# 02_CV25_SOM.net
KiCad netlist of a schematic drawn in Altium Designer
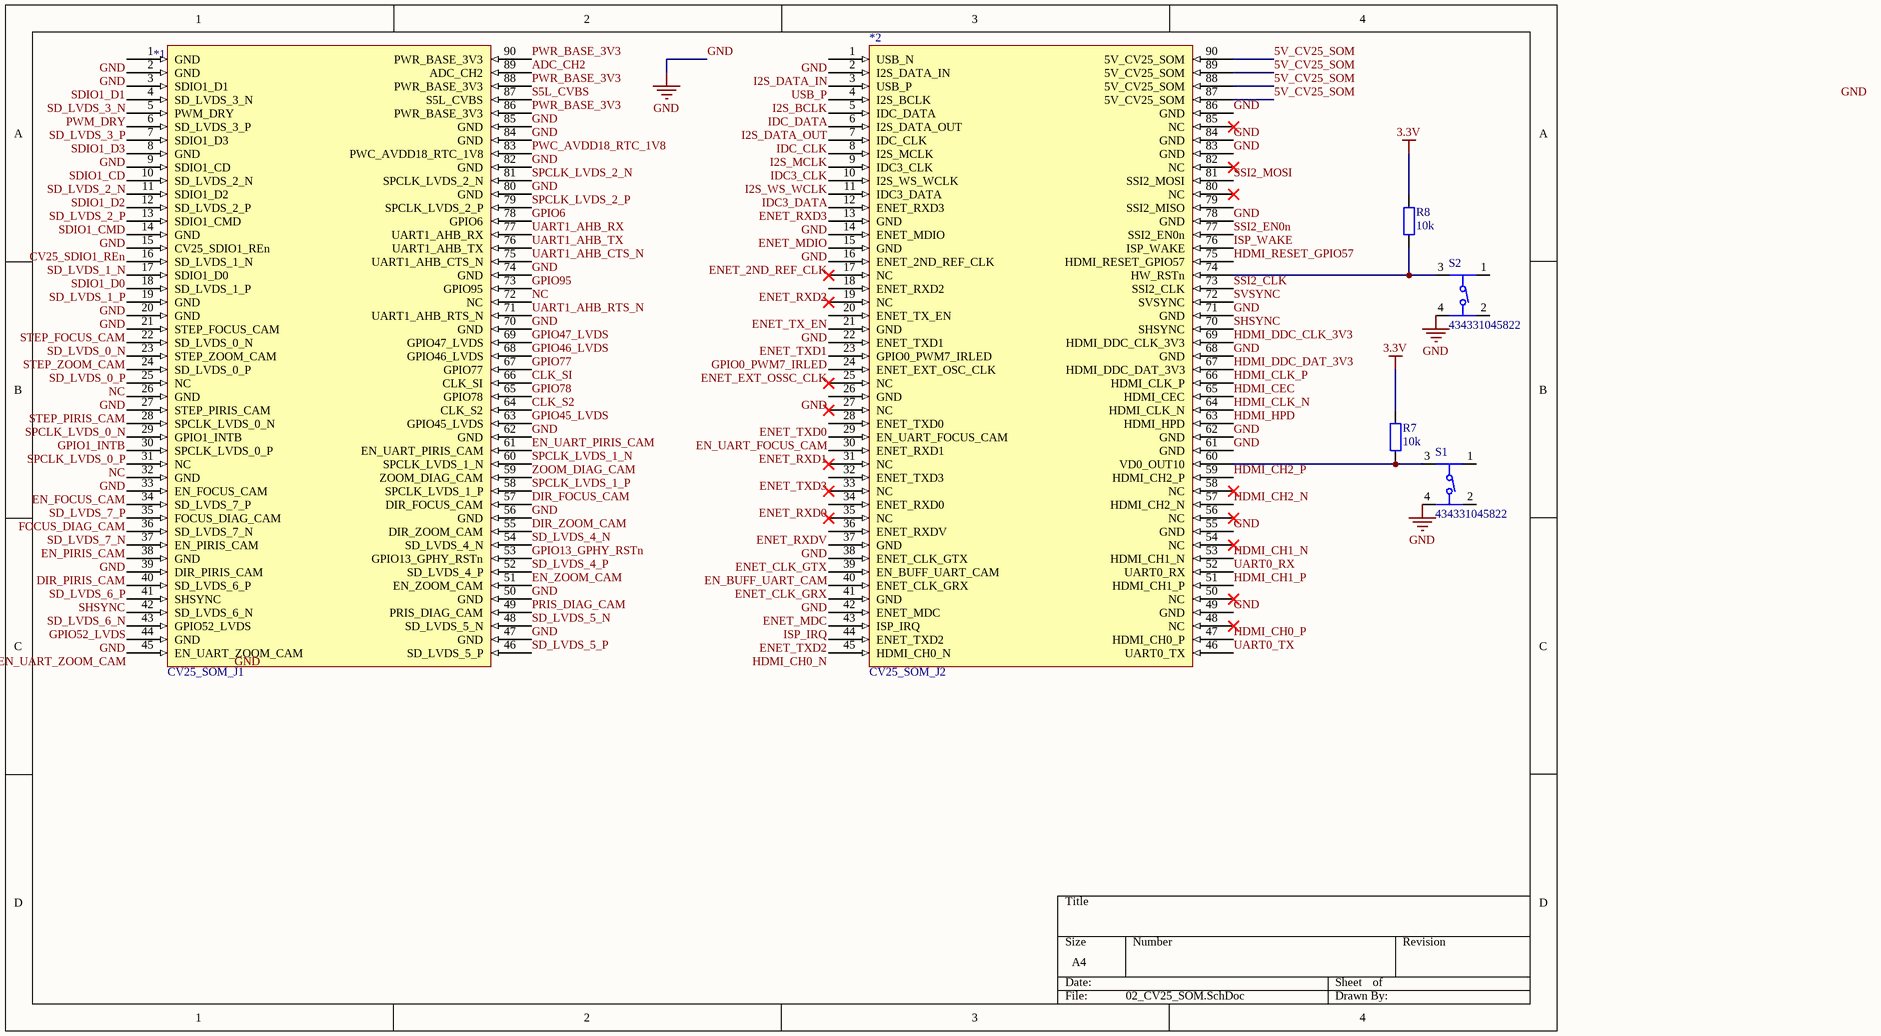
[diagram p0: 02_CV25_SOM.SchDoc]

(export (version "E")
  (design (tool "Eeschema 10.0.6"))
  (components
    (comp (ref "*1")
      (value "CV25_SOM_J1")
      (footprint "HIROSE_DF40C-90DS-0.4V(51)")
      (libsource (lib "MyLib") (part "CV25_SOM_J1"))
    )
    (comp (ref "*2")
      (value "CV25_SOM_J2")
      (footprint "HIROSE_DF40C-90DS-0.4V(51)")
      (libsource (lib "MyLib") (part "CV25_SOM_J2"))
    )
    (comp (ref "R7")
      (value "10k")
      (footprint "tro smd 0603")
      (description "Dán")
      (libsource (lib "Altium_Lib_by_KhueNguyenCreator") (part "Tro 0603 1% 10k"))
    )
    (comp (ref "R8")
      (value "10k")
      (footprint "tro smd 0603")
      (description "Dán")
      (libsource (lib "Altium_Lib_by_KhueNguyenCreator") (part "Tro 0603 1% 10k"))
    )
    (comp (ref "S1")
      (value "434331045822")
      (footprint "4343X10458XX")
      (fields (field (name "MF") "{'manufacturer': u'~{W}xfcrth Elektronik'}"))
      (libsource (lib "434331045822") (part "434331045822"))
    )
    (comp (ref "S2")
      (value "434331045822")
      (footprint "4343X10458XX")
      (fields (field (name "MF") "{'manufacturer': u'~{W}xfcrth Elektronik'}"))
      (libsource (lib "434331045822") (part "434331045822"))
    )
  )
  (nets
    (net (code "1") (name "/5V_CV25_SOM") (class "Default")
      (node (ref "*2") (pin "87") (pinfunction "5V_CV25_SOM_87") (pintype "input"))
      (node (ref "*2") (pin "88") (pinfunction "5V_CV25_SOM_88") (pintype "input"))
      (node (ref "*2") (pin "89") (pinfunction "5V_CV25_SOM_89") (pintype "input"))
      (node (ref "*2") (pin "90") (pinfunction "5V_CV25_SOM_90") (pintype "input"))
    )
    (net (code "2") (name "/ADC_CH2") (class "Default")
      (node (ref "*1") (pin "89") (pinfunction "ADC_CH2_89") (pintype "input"))
    )
    (net (code "3") (name "/CLK_S2") (class "Default")
      (node (ref "*1") (pin "64") (pinfunction "CLK_S2_64") (pintype "input"))
    )
    (net (code "4") (name "/CLK_SI") (class "Default")
      (node (ref "*1") (pin "66") (pinfunction "CLK_SI_66") (pintype "input"))
    )
    (net (code "5") (name "/CV25_SDIO1_REn") (class "Default")
      (node (ref "*1") (pin "15") (pinfunction "CV25_SDIO1_REn_15") (pintype "input"))
    )
    (net (code "6") (name "/DIR_FOCUS_CAM") (class "Default")
      (node (ref "*1") (pin "57") (pinfunction "DIR_FOCUS_CAM_57") (pintype "input"))
    )
    (net (code "7") (name "/DIR_PIRIS_CAM") (class "Default")
      (node (ref "*1") (pin "39") (pinfunction "DIR_PIRIS_CAM_39") (pintype "input"))
    )
    (net (code "8") (name "/DIR_ZOOM_CAM") (class "Default")
      (node (ref "*1") (pin "55") (pinfunction "DIR_ZOOM_CAM_55") (pintype "input"))
    )
    (net (code "9") (name "/ENET_2ND_REF_CLK") (class "Default")
      (node (ref "*2") (pin "16") (pinfunction "ENET_2ND_REF_CLK_16") (pintype "input"))
    )
    (net (code "10") (name "/ENET_CLK_GRX") (class "Default")
      (node (ref "*2") (pin "40") (pinfunction "ENET_CLK_GRX_40") (pintype "input"))
    )
    (net (code "11") (name "/ENET_CLK_GTX") (class "Default")
      (node (ref "*2") (pin "38") (pinfunction "ENET_CLK_GTX_38") (pintype "input"))
    )
    (net (code "12") (name "/ENET_EXT_OSSC_CLK") (class "Default")
      (node (ref "*2") (pin "24") (pinfunction "ENET_EXT_OSC_CLK_24") (pintype "input"))
    )
    (net (code "13") (name "/ENET_MDC") (class "Default")
      (node (ref "*2") (pin "42") (pinfunction "ENET_MDC_42") (pintype "input"))
    )
    (net (code "14") (name "/ENET_MDIO") (class "Default")
      (node (ref "*2") (pin "14") (pinfunction "ENET_MDIO_14") (pintype "input"))
    )
    (net (code "15") (name "/ENET_RXD0") (class "Default")
      (node (ref "*2") (pin "34") (pinfunction "ENET_RXD0_34") (pintype "input"))
    )
    (net (code "16") (name "/ENET_RXD1") (class "Default")
      (node (ref "*2") (pin "30") (pinfunction "ENET_RXD1_30") (pintype "input"))
    )
    (net (code "17") (name "/ENET_RXD2") (class "Default")
      (node (ref "*2") (pin "18") (pinfunction "ENET_RXD2_18") (pintype "input"))
    )
    (net (code "18") (name "/ENET_RXD3") (class "Default")
      (node (ref "*2") (pin "12") (pinfunction "ENET_RXD3_12") (pintype "input"))
    )
    (net (code "19") (name "/ENET_RXDV") (class "Default")
      (node (ref "*2") (pin "36") (pinfunction "ENET_RXDV_36") (pintype "input"))
    )
    (net (code "20") (name "/ENET_TXD0") (class "Default")
      (node (ref "*2") (pin "28") (pinfunction "ENET_TXD0_28") (pintype "input"))
    )
    (net (code "21") (name "/ENET_TXD1") (class "Default")
      (node (ref "*2") (pin "22") (pinfunction "ENET_TXD1_22") (pintype "input"))
    )
    (net (code "22") (name "/ENET_TXD2") (class "Default")
      (node (ref "*2") (pin "44") (pinfunction "ENET_TXD2_44") (pintype "input"))
    )
    (net (code "23") (name "/ENET_TXD3") (class "Default")
      (node (ref "*2") (pin "32") (pinfunction "ENET_TXD3_32") (pintype "input"))
    )
    (net (code "24") (name "/ENET_TX_EN") (class "Default")
      (node (ref "*2") (pin "20") (pinfunction "ENET_TX_EN_20") (pintype "input"))
    )
    (net (code "25") (name "/EN_BUFF_UART_CAM") (class "Default")
      (node (ref "*2") (pin "39") (pinfunction "EN_BUFF_UART_CAM_39") (pintype "input"))
    )
    (net (code "26") (name "/EN_FOCUS_CAM") (class "Default")
      (node (ref "*1") (pin "33") (pinfunction "EN_FOCUS_CAM_33") (pintype "input"))
    )
    (net (code "27") (name "/EN_PIRIS_CAM") (class "Default")
      (node (ref "*1") (pin "37") (pinfunction "EN_PIRIS_CAM_37") (pintype "input"))
    )
    (net (code "28") (name "/EN_UART_FOCUS_CAM") (class "Default")
      (node (ref "*2") (pin "29") (pinfunction "EN_UART_FOCUS_CAM_29") (pintype "input"))
    )
    (net (code "29") (name "/EN_UART_PIRIS_CAM") (class "Default")
      (node (ref "*1") (pin "61") (pinfunction "EN_UART_PIRIS_CAM_61") (pintype "input"))
    )
    (net (code "30") (name "/EN_UART_ZOOM_CAM") (class "Default")
      (node (ref "*1") (pin "45") (pinfunction "EN_UART_ZOOM_CAM_45") (pintype "input"))
    )
    (net (code "31") (name "/EN_ZOOM_CAM") (class "Default")
      (node (ref "*1") (pin "51") (pinfunction "EN_ZOOM_CAM_51") (pintype "input"))
    )
    (net (code "32") (name "/FOCUS_DIAG_CAM") (class "Default")
      (node (ref "*1") (pin "35") (pinfunction "FOCUS_DIAG_CAM_35") (pintype "input"))
    )
    (net (code "33") (name "/GPIO0_PWM7_IRLED") (class "Default")
      (node (ref "*2") (pin "23") (pinfunction "GPIO0_PWM7_IRLED_23") (pintype "input"))
    )
    (net (code "34") (name "/GPIO1_INTB") (class "Default")
      (node (ref "*1") (pin "29") (pinfunction "GPIO1_INTB_29") (pintype "input"))
    )
    (net (code "35") (name "/GPIO6") (class "Default")
      (node (ref "*1") (pin "78") (pinfunction "GPIO6_78") (pintype "input"))
    )
    (net (code "36") (name "/GPIO13_GPHY_RSTn") (class "Default")
      (node (ref "*1") (pin "53") (pinfunction "GPIO13_GPHY_RSTn_53") (pintype "input"))
    )
    (net (code "37") (name "/GPIO45_LVDS") (class "Default")
      (node (ref "*1") (pin "63") (pinfunction "GPIO45_LVDS_63") (pintype "input"))
    )
    (net (code "38") (name "/GPIO46_LVDS") (class "Default")
      (node (ref "*1") (pin "68") (pinfunction "GPIO46_LVDS_68") (pintype "input"))
    )
    (net (code "39") (name "/GPIO47_LVDS") (class "Default")
      (node (ref "*1") (pin "69") (pinfunction "GPIO47_LVDS_69") (pintype "input"))
    )
    (net (code "40") (name "/GPIO52_LVDS") (class "Default")
      (node (ref "*1") (pin "43") (pinfunction "GPIO52_LVDS_43") (pintype "input"))
    )
    (net (code "41") (name "/GPIO77") (class "Default")
      (node (ref "*1") (pin "67") (pinfunction "GPIO77_67") (pintype "input"))
    )
    (net (code "42") (name "/GPIO78") (class "Default")
      (node (ref "*1") (pin "65") (pinfunction "GPIO78_65") (pintype "input"))
    )
    (net (code "43") (name "/GPIO95") (class "Default")
      (node (ref "*1") (pin "73") (pinfunction "GPIO95_73") (pintype "input"))
    )
    (net (code "44") (name "/HDMI_CEC") (class "Default")
      (node (ref "*2") (pin "65") (pinfunction "HDMI_CEC_65") (pintype "input"))
    )
    (net (code "45") (name "/HDMI_CH0_N") (class "Default")
      (node (ref "*2") (pin "45") (pinfunction "HDMI_CH0_N_45") (pintype "input"))
    )
    (net (code "46") (name "/HDMI_CH0_P") (class "Default")
      (node (ref "*2") (pin "47") (pinfunction "HDMI_CH0_P_47") (pintype "input"))
    )
    (net (code "47") (name "/HDMI_CH1_N") (class "Default")
      (node (ref "*2") (pin "53") (pinfunction "HDMI_CH1_N_53") (pintype "input"))
    )
    (net (code "48") (name "/HDMI_CH1_P") (class "Default")
      (node (ref "*2") (pin "51") (pinfunction "HDMI_CH1_P_51") (pintype "input"))
    )
    (net (code "49") (name "/HDMI_CH2_N") (class "Default")
      (node (ref "*2") (pin "57") (pinfunction "HDMI_CH2_N_57") (pintype "input"))
    )
    (net (code "50") (name "/HDMI_CH2_P") (class "Default")
      (node (ref "*2") (pin "59") (pinfunction "HDMI_CH2_P_59") (pintype "input"))
    )
    (net (code "51") (name "/HDMI_CLK_N") (class "Default")
      (node (ref "*2") (pin "64") (pinfunction "HDMI_CLK_N_64") (pintype "input"))
    )
    (net (code "52") (name "/HDMI_CLK_P") (class "Default")
      (node (ref "*2") (pin "66") (pinfunction "HDMI_CLK_P_66") (pintype "input"))
    )
    (net (code "53") (name "/HDMI_DDC_CLK_3V3") (class "Default")
      (node (ref "*2") (pin "69") (pinfunction "HDMI_DDC_CLK_3V3_69") (pintype "input"))
    )
    (net (code "54") (name "/HDMI_DDC_DAT_3V3") (class "Default")
      (node (ref "*2") (pin "67") (pinfunction "HDMI_DDC_DAT_3V3_67") (pintype "input"))
    )
    (net (code "55") (name "/HDMI_HPD") (class "Default")
      (node (ref "*2") (pin "63") (pinfunction "HDMI_HPD_63") (pintype "input"))
    )
    (net (code "56") (name "/HDMI_RESET_GPIO57") (class "Default")
      (node (ref "*2") (pin "75") (pinfunction "HDMI_RESET_GPIO57_75") (pintype "input"))
    )
    (net (code "57") (name "/I2S_BCLK") (class "Default")
      (node (ref "*2") (pin "4") (pinfunction "I2S_BCLK_4") (pintype "input"))
    )
    (net (code "58") (name "/I2S_DATA_IN") (class "Default")
      (node (ref "*2") (pin "2") (pinfunction "I2S_DATA_IN_2") (pintype "input"))
    )
    (net (code "59") (name "/I2S_DATA_OUT") (class "Default")
      (node (ref "*2") (pin "6") (pinfunction "I2S_DATA_OUT_6") (pintype "input"))
    )
    (net (code "60") (name "/I2S_MCLK") (class "Default")
      (node (ref "*2") (pin "8") (pinfunction "I2S_MCLK_8") (pintype "input"))
    )
    (net (code "61") (name "/I2S_WS_WCLK") (class "Default")
      (node (ref "*2") (pin "10") (pinfunction "I2S_WS_WCLK_10") (pintype "input"))
    )
    (net (code "62") (name "/IDC3_CLK") (class "Default")
      (node (ref "*2") (pin "9") (pinfunction "IDC3_CLK_9") (pintype "input"))
    )
    (net (code "63") (name "/IDC3_DATA") (class "Default")
      (node (ref "*2") (pin "11") (pinfunction "IDC3_DATA_11") (pintype "input"))
    )
    (net (code "64") (name "/IDC_CLK") (class "Default")
      (node (ref "*2") (pin "7") (pinfunction "IDC_CLK_7") (pintype "input"))
    )
    (net (code "65") (name "/IDC_DATA") (class "Default")
      (node (ref "*2") (pin "5") (pinfunction "IDC_DATA_5") (pintype "input"))
    )
    (net (code "66") (name "/ISP_IRQ") (class "Default")
      (node (ref "*2") (pin "43") (pinfunction "ISP_IRQ_43") (pintype "input"))
    )
    (net (code "67") (name "/ISP_WAKE") (class "Default")
      (node (ref "*2") (pin "76") (pinfunction "ISP_WAKE_76") (pintype "input"))
    )
    (net (code "68") (name "/NC") (class "Default")
      (node (ref "*1") (pin "25") (pinfunction "NC_25") (pintype "input"))
      (node (ref "*1") (pin "31") (pinfunction "NC_31") (pintype "input"))
      (node (ref "*1") (pin "72") (pinfunction "NC_72") (pintype "input"))
    )
    (net (code "69") (name "/PRIS_DIAG_CAM") (class "Default")
      (node (ref "*1") (pin "49") (pinfunction "PRIS_DIAG_CAM_49") (pintype "input"))
    )
    (net (code "70") (name "/PWC_AVDD18_RTC_1V8") (class "Default")
      (node (ref "*1") (pin "83") (pinfunction "PWC_AVDD18_RTC_1V8_83") (pintype "input"))
    )
    (net (code "71") (name "/PWM_DRY") (class "Default")
      (node (ref "*1") (pin "5") (pinfunction "PWM_DRY_5") (pintype "input"))
    )
    (net (code "72") (name "/PWR_BASE_3V3") (class "Default")
      (node (ref "*1") (pin "86") (pinfunction "PWR_BASE_3V3_86") (pintype "input"))
      (node (ref "*1") (pin "88") (pinfunction "PWR_BASE_3V3_88") (pintype "input"))
      (node (ref "*1") (pin "90") (pinfunction "PWR_BASE_3V3_90") (pintype "input"))
    )
    (net (code "73") (name "/S5L_CVBS") (class "Default")
      (node (ref "*1") (pin "87") (pinfunction "S5L_CVBS_87") (pintype "input"))
    )
    (net (code "74") (name "/SDIO1_CD") (class "Default")
      (node (ref "*1") (pin "9") (pinfunction "SDIO1_CD_9") (pintype "input"))
    )
    (net (code "75") (name "/SDIO1_CMD") (class "Default")
      (node (ref "*1") (pin "13") (pinfunction "SDIO1_CMD_13") (pintype "input"))
    )
    (net (code "76") (name "/SDIO1_D0") (class "Default")
      (node (ref "*1") (pin "17") (pinfunction "SDIO1_D0_17") (pintype "input"))
    )
    (net (code "77") (name "/SDIO1_D1") (class "Default")
      (node (ref "*1") (pin "3") (pinfunction "SDIO1_D1_3") (pintype "input"))
    )
    (net (code "78") (name "/SDIO1_D2") (class "Default")
      (node (ref "*1") (pin "11") (pinfunction "SDIO1_D2_11") (pintype "input"))
    )
    (net (code "79") (name "/SDIO1_D3") (class "Default")
      (node (ref "*1") (pin "7") (pinfunction "SDIO1_D3_7") (pintype "input"))
    )
    (net (code "80") (name "/SD_LVDS_0_N") (class "Default")
      (node (ref "*1") (pin "22") (pinfunction "SD_LVDS_0_N_22") (pintype "input"))
    )
    (net (code "81") (name "/SD_LVDS_0_P") (class "Default")
      (node (ref "*1") (pin "24") (pinfunction "SD_LVDS_0_P_24") (pintype "input"))
    )
    (net (code "82") (name "/SD_LVDS_1_N") (class "Default")
      (node (ref "*1") (pin "16") (pinfunction "SD_LVDS_1_N_16") (pintype "input"))
    )
    (net (code "83") (name "/SD_LVDS_1_P") (class "Default")
      (node (ref "*1") (pin "18") (pinfunction "SD_LVDS_1_P_18") (pintype "input"))
    )
    (net (code "84") (name "/SD_LVDS_2_N") (class "Default")
      (node (ref "*1") (pin "10") (pinfunction "SD_LVDS_2_N_10") (pintype "input"))
    )
    (net (code "85") (name "/SD_LVDS_2_P") (class "Default")
      (node (ref "*1") (pin "12") (pinfunction "SD_LVDS_2_P_12") (pintype "input"))
    )
    (net (code "86") (name "/SD_LVDS_3_N") (class "Default")
      (node (ref "*1") (pin "4") (pinfunction "SD_LVDS_3_N_4") (pintype "input"))
    )
    (net (code "87") (name "/SD_LVDS_3_P") (class "Default")
      (node (ref "*1") (pin "6") (pinfunction "SD_LVDS_3_P_6") (pintype "input"))
    )
    (net (code "88") (name "/SD_LVDS_4_N") (class "Default")
      (node (ref "*1") (pin "54") (pinfunction "SD_LVDS_4_N_54") (pintype "input"))
    )
    (net (code "89") (name "/SD_LVDS_4_P") (class "Default")
      (node (ref "*1") (pin "52") (pinfunction "SD_LVDS_4_P_52") (pintype "input"))
    )
    (net (code "90") (name "/SD_LVDS_5_N") (class "Default")
      (node (ref "*1") (pin "48") (pinfunction "SD_LVDS_5_N_48") (pintype "input"))
    )
    (net (code "91") (name "/SD_LVDS_5_P") (class "Default")
      (node (ref "*1") (pin "46") (pinfunction "SD_LVDS_5_P_46") (pintype "input"))
    )
    (net (code "92") (name "/SD_LVDS_6_N") (class "Default")
      (node (ref "*1") (pin "42") (pinfunction "SD_LVDS_6_N_42") (pintype "input"))
    )
    (net (code "93") (name "/SD_LVDS_6_P") (class "Default")
      (node (ref "*1") (pin "40") (pinfunction "SD_LVDS_6_P_40") (pintype "input"))
    )
    (net (code "94") (name "/SD_LVDS_7_N") (class "Default")
      (node (ref "*1") (pin "36") (pinfunction "SD_LVDS_7_N_36") (pintype "input"))
    )
    (net (code "95") (name "/SD_LVDS_7_P") (class "Default")
      (node (ref "*1") (pin "34") (pinfunction "SD_LVDS_7_P_34") (pintype "input"))
    )
    (net (code "96") (name "/SHSYNC") (class "Default")
      (node (ref "*1") (pin "41") (pinfunction "SHSYNC_41") (pintype "input"))
      (node (ref "*2") (pin "70") (pinfunction "SHSYNC_70") (pintype "input"))
    )
    (net (code "97") (name "/SPCLK_LVDS_0_N") (class "Default")
      (node (ref "*1") (pin "28") (pinfunction "SPCLK_LVDS_0_N_28") (pintype "input"))
    )
    (net (code "98") (name "/SPCLK_LVDS_0_P") (class "Default")
      (node (ref "*1") (pin "30") (pinfunction "SPCLK_LVDS_0_P_30") (pintype "input"))
    )
    (net (code "99") (name "/SPCLK_LVDS_1_N") (class "Default")
      (node (ref "*1") (pin "60") (pinfunction "SPCLK_LVDS_1_N_60") (pintype "input"))
    )
    (net (code "100") (name "/SPCLK_LVDS_1_P") (class "Default")
      (node (ref "*1") (pin "58") (pinfunction "SPCLK_LVDS_1_P_58") (pintype "input"))
    )
    (net (code "101") (name "/SPCLK_LVDS_2_N") (class "Default")
      (node (ref "*1") (pin "81") (pinfunction "SPCLK_LVDS_2_N_81") (pintype "input"))
    )
    (net (code "102") (name "/SPCLK_LVDS_2_P") (class "Default")
      (node (ref "*1") (pin "79") (pinfunction "SPCLK_LVDS_2_P_79") (pintype "input"))
    )
    (net (code "103") (name "/SSI2_CLK") (class "Default")
      (node (ref "*2") (pin "73") (pinfunction "SSI2_CLK_73") (pintype "input"))
    )
    (net (code "104") (name "/SSI2_EN0n") (class "Default")
      (node (ref "*2") (pin "77") (pinfunction "SSI2_EN0n_77") (pintype "input"))
    )
    (net (code "105") (name "/SSI2_MOSI") (class "Default")
      (node (ref "*2") (pin "81") (pinfunction "SSI2_MOSI_81") (pintype "input"))
    )
    (net (code "106") (name "/STEP_FOCUS_CAM") (class "Default")
      (node (ref "*1") (pin "21") (pinfunction "STEP_FOCUS_CAM_21") (pintype "input"))
    )
    (net (code "107") (name "/STEP_PIRIS_CAM") (class "Default")
      (node (ref "*1") (pin "27") (pinfunction "STEP_PIRIS_CAM_27") (pintype "input"))
    )
    (net (code "108") (name "/STEP_ZOOM_CAM") (class "Default")
      (node (ref "*1") (pin "23") (pinfunction "STEP_ZOOM_CAM_23") (pintype "input"))
    )
    (net (code "109") (name "/SVSYNC") (class "Default")
      (node (ref "*2") (pin "72") (pinfunction "SVSYNC_72") (pintype "input"))
    )
    (net (code "110") (name "/UART0_RX") (class "Default")
      (node (ref "*2") (pin "52") (pinfunction "UART0_RX_52") (pintype "input"))
    )
    (net (code "111") (name "/UART0_TX") (class "Default")
      (node (ref "*2") (pin "46") (pinfunction "UART0_TX_46") (pintype "input"))
    )
    (net (code "112") (name "/UART1_AHB_CTS_N") (class "Default")
      (node (ref "*1") (pin "75") (pinfunction "UART1_AHB_CTS_N_75") (pintype "input"))
    )
    (net (code "113") (name "/UART1_AHB_RTS_N") (class "Default")
      (node (ref "*1") (pin "71") (pinfunction "UART1_AHB_RTS_N_71") (pintype "input"))
    )
    (net (code "114") (name "/UART1_AHB_RX") (class "Default")
      (node (ref "*1") (pin "77") (pinfunction "UART1_AHB_RX_77") (pintype "input"))
    )
    (net (code "115") (name "/UART1_AHB_TX") (class "Default")
      (node (ref "*1") (pin "76") (pinfunction "UART1_AHB_TX_76") (pintype "input"))
    )
    (net (code "116") (name "/USB_P") (class "Default")
      (node (ref "*2") (pin "3") (pinfunction "USB_P_3") (pintype "input"))
    )
    (net (code "117") (name "/ZOOM_DIAG_CAM") (class "Default")
      (node (ref "*1") (pin "59") (pinfunction "ZOOM_DIAG_CAM_59") (pintype "input"))
    )
    (net (code "118") (name "3.3V") (class "Default")
      (node (ref "R7") (pin "2") (pinfunction "2_2") (pintype "passive"))
      (node (ref "R8") (pin "2") (pinfunction "2_2") (pintype "passive"))
    )
    (net (code "119") (name "GND") (class "Default")
      (node (ref "*1") (pin "1") (pinfunction "GND_1") (pintype "input"))
      (node (ref "*1") (pin "14") (pinfunction "GND_14") (pintype "input"))
      (node (ref "*1") (pin "19") (pinfunction "GND_19") (pintype "input"))
      (node (ref "*1") (pin "2") (pinfunction "GND_2") (pintype "input"))
      (node (ref "*1") (pin "20") (pinfunction "GND_20") (pintype "input"))
      (node (ref "*1") (pin "26") (pinfunction "GND_26") (pintype "input"))
      (node (ref "*1") (pin "32") (pinfunction "GND_32") (pintype "input"))
      (node (ref "*1") (pin "38") (pinfunction "GND_38") (pintype "input"))
      (node (ref "*1") (pin "44") (pinfunction "GND_44") (pintype "input"))
      (node (ref "*1") (pin "47") (pinfunction "GND_47") (pintype "input"))
      (node (ref "*1") (pin "50") (pinfunction "GND_50") (pintype "input"))
      (node (ref "*1") (pin "56") (pinfunction "GND_56") (pintype "input"))
      (node (ref "*1") (pin "62") (pinfunction "GND_62") (pintype "input"))
      (node (ref "*1") (pin "70") (pinfunction "GND_70") (pintype "input"))
      (node (ref "*1") (pin "74") (pinfunction "GND_74") (pintype "input"))
      (node (ref "*1") (pin "8") (pinfunction "GND_8") (pintype "input"))
      (node (ref "*1") (pin "80") (pinfunction "GND_80") (pintype "input"))
      (node (ref "*1") (pin "82") (pinfunction "GND_82") (pintype "input"))
      (node (ref "*1") (pin "84") (pinfunction "GND_84") (pintype "input"))
      (node (ref "*1") (pin "85") (pinfunction "GND_85") (pintype "input"))
      (node (ref "*2") (pin "1") (pinfunction "USB_N_1") (pintype "input"))
      (node (ref "*2") (pin "13") (pinfunction "GND_13") (pintype "input"))
      (node (ref "*2") (pin "15") (pinfunction "GND_15") (pintype "input"))
      (node (ref "*2") (pin "21") (pinfunction "GND_21") (pintype "input"))
      (node (ref "*2") (pin "26") (pinfunction "GND_26") (pintype "input"))
      (node (ref "*2") (pin "37") (pinfunction "GND_37") (pintype "input"))
      (node (ref "*2") (pin "41") (pinfunction "GND_41") (pintype "input"))
      (node (ref "*2") (pin "49") (pinfunction "GND_49") (pintype "input"))
      (node (ref "*2") (pin "55") (pinfunction "GND_55") (pintype "input"))
      (node (ref "*2") (pin "61") (pinfunction "GND_61") (pintype "input"))
      (node (ref "*2") (pin "62") (pinfunction "GND_62") (pintype "input"))
      (node (ref "*2") (pin "68") (pinfunction "GND_68") (pintype "input"))
      (node (ref "*2") (pin "71") (pinfunction "GND_71") (pintype "input"))
      (node (ref "*2") (pin "78") (pinfunction "GND_78") (pintype "input"))
      (node (ref "*2") (pin "83") (pinfunction "GND_83") (pintype "input"))
      (node (ref "*2") (pin "84") (pinfunction "GND_84") (pintype "input"))
      (node (ref "*2") (pin "86") (pinfunction "GND_86") (pintype "input"))
      (node (ref "S1") (pin "4") (pinfunction "2_4") (pintype "passive"))
      (node (ref "S2") (pin "4") (pinfunction "2_4") (pintype "passive"))
    )
    (net (code "120") (name "Net-(*2-HW_RSTn)") (class "Default")
      (node (ref "*2") (pin "74") (pinfunction "HW_RSTn_74") (pintype "input"))
      (node (ref "R8") (pin "1") (pinfunction "1_1") (pintype "passive"))
      (node (ref "S2") (pin "3") (pinfunction "1_3") (pintype "passive"))
    )
    (net (code "121") (name "Net-(*2-VD0_OUT10)") (class "Default")
      (node (ref "*2") (pin "60") (pinfunction "VD0_OUT10_60") (pintype "input"))
      (node (ref "R7") (pin "1") (pinfunction "1_1") (pintype "passive"))
      (node (ref "S1") (pin "3") (pinfunction "1_3") (pintype "passive"))
    )
    (net (code "122") (name "unconnected-(*2-NC-Pad17)") (class "Default")
      (node (ref "*2") (pin "17") (pinfunction "NC_17") (pintype "input+no_connect"))
    )
    (net (code "123") (name "unconnected-(*2-NC-Pad19)") (class "Default")
      (node (ref "*2") (pin "19") (pinfunction "NC_19") (pintype "input+no_connect"))
    )
    (net (code "124") (name "unconnected-(*2-NC-Pad25)") (class "Default")
      (node (ref "*2") (pin "25") (pinfunction "NC_25") (pintype "input+no_connect"))
    )
    (net (code "125") (name "unconnected-(*2-NC-Pad27)") (class "Default")
      (node (ref "*2") (pin "27") (pinfunction "NC_27") (pintype "input+no_connect"))
    )
    (net (code "126") (name "unconnected-(*2-NC-Pad31)") (class "Default")
      (node (ref "*2") (pin "31") (pinfunction "NC_31") (pintype "input+no_connect"))
    )
    (net (code "127") (name "unconnected-(*2-NC-Pad33)") (class "Default")
      (node (ref "*2") (pin "33") (pinfunction "NC_33") (pintype "input+no_connect"))
    )
    (net (code "128") (name "unconnected-(*2-NC-Pad35)") (class "Default")
      (node (ref "*2") (pin "35") (pinfunction "NC_35") (pintype "input+no_connect"))
    )
    (net (code "129") (name "unconnected-(*2-NC-Pad48)") (class "Default")
      (node (ref "*2") (pin "48") (pinfunction "NC_48") (pintype "input+no_connect"))
    )
    (net (code "130") (name "unconnected-(*2-NC-Pad50)") (class "Default")
      (node (ref "*2") (pin "50") (pinfunction "NC_50") (pintype "input+no_connect"))
    )
    (net (code "131") (name "unconnected-(*2-NC-Pad54)") (class "Default")
      (node (ref "*2") (pin "54") (pinfunction "NC_54") (pintype "input+no_connect"))
    )
    (net (code "132") (name "unconnected-(*2-NC-Pad56)") (class "Default")
      (node (ref "*2") (pin "56") (pinfunction "NC_56") (pintype "input+no_connect"))
    )
    (net (code "133") (name "unconnected-(*2-NC-Pad58)") (class "Default")
      (node (ref "*2") (pin "58") (pinfunction "NC_58") (pintype "input+no_connect"))
    )
    (net (code "134") (name "unconnected-(*2-NC-Pad80)") (class "Default")
      (node (ref "*2") (pin "80") (pinfunction "NC_80") (pintype "input+no_connect"))
    )
    (net (code "135") (name "unconnected-(*2-NC-Pad82)") (class "Default")
      (node (ref "*2") (pin "82") (pinfunction "NC_82") (pintype "input+no_connect"))
    )
    (net (code "136") (name "unconnected-(*2-NC-Pad85)") (class "Default")
      (node (ref "*2") (pin "85") (pinfunction "NC_85") (pintype "input+no_connect"))
    )
    (net (code "137") (name "unconnected-(*2-SSI2_MISO-Pad79)") (class "Default")
      (node (ref "*2") (pin "79") (pinfunction "SSI2_MISO_79") (pintype "input"))
    )
    (net (code "138") (name "unconnected-(S1-3-Pad1)") (class "Default")
      (node (ref "S1") (pin "1") (pinfunction "3_1") (pintype "passive"))
    )
    (net (code "139") (name "unconnected-(S1-4-Pad2)") (class "Default")
      (node (ref "S1") (pin "2") (pinfunction "4_2") (pintype "passive"))
    )
    (net (code "140") (name "unconnected-(S2-3-Pad1)") (class "Default")
      (node (ref "S2") (pin "1") (pinfunction "3_1") (pintype "passive"))
    )
    (net (code "141") (name "unconnected-(S2-4-Pad2)") (class "Default")
      (node (ref "S2") (pin "2") (pinfunction "4_2") (pintype "passive"))
    )
  )
)
